# MZCAT_color_sensor.net
KiCad netlist of a schematic drawn in Altium Designer
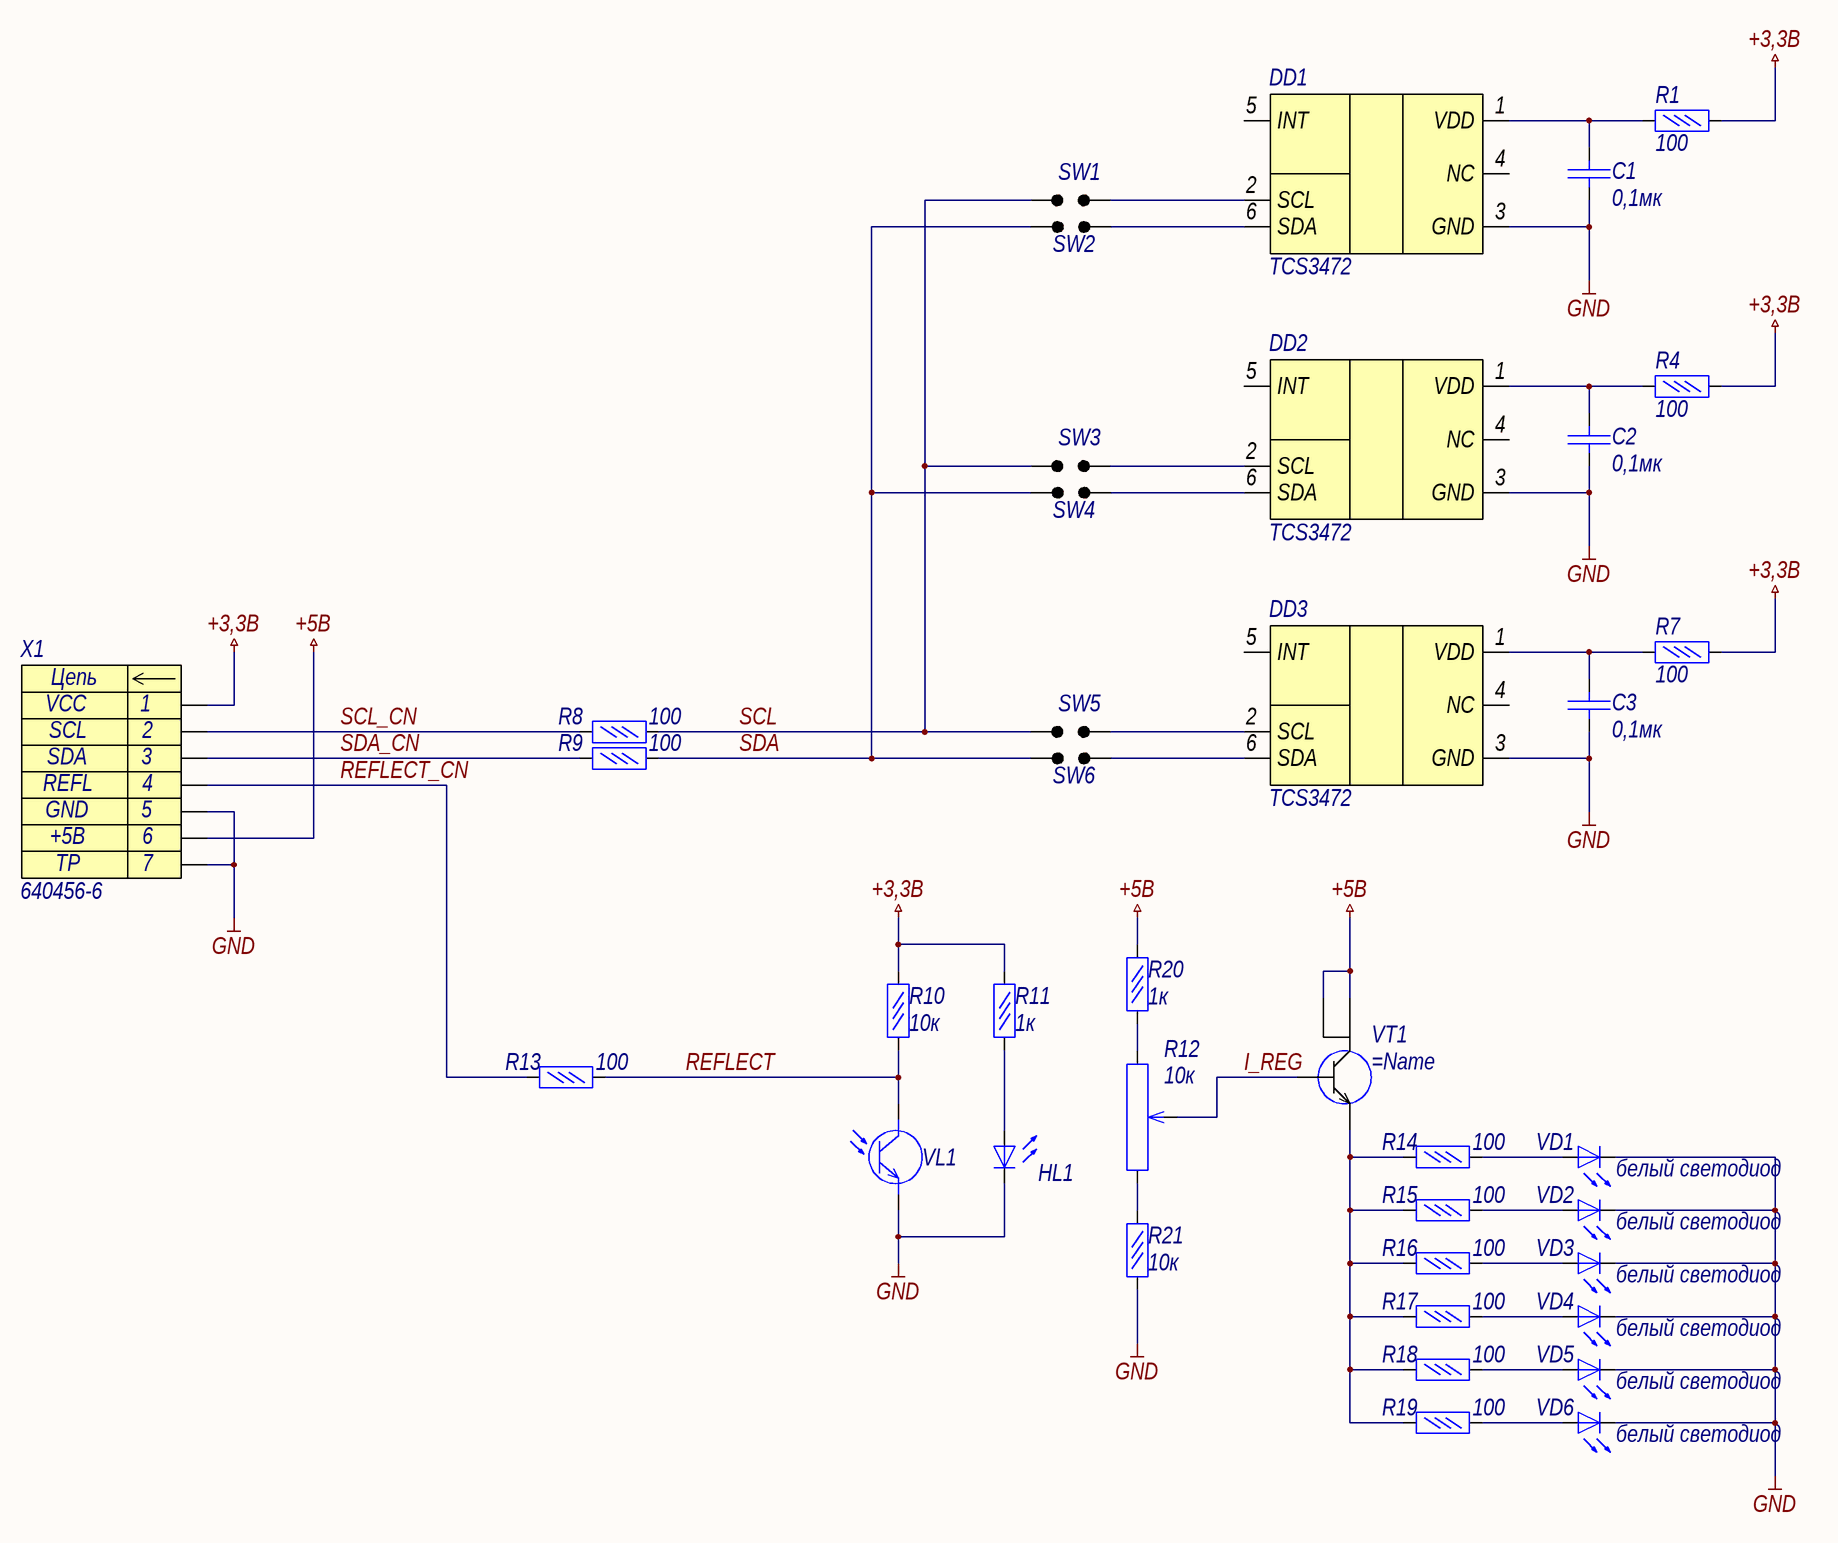
[diagram p0: MZCAT_color_sensor.SchDoc]

(export (version "E")
  (design (tool "Eeschema 10.0.6"))
  (components
    (comp (ref "DD1")
      (value "TCS3472")
      (footprint "TCS3472")
      (libsource (lib "MZBT_SchLibrary") (part "TCS3472"))
    )
    (comp (ref "DD2")
      (value "TCS3472")
      (footprint "TCS3472")
      (libsource (lib "MZBT_SchLibrary") (part "TCS3472"))
    )
    (comp (ref "DD3")
      (value "TCS3472")
      (footprint "TCS3472")
      (libsource (lib "MZBT_SchLibrary") (part "TCS3472"))
    )
    (comp (ref "HL1")
      (value "~")
      (footprint "LED 5mm")
      (description "инфракрасный светодиод")
      (libsource (lib "MZBT_SchLibrary") (part "ИК светодиод"))
    )
    (comp (ref "R1")
      (value "100")
      (footprint "R0603")
      (description "Резистор 0,05Вт")
      (libsource (lib "MZBT_SchLibrary") (part "Резистор 0.05Вт"))
    )
    (comp (ref "R4")
      (value "100")
      (footprint "R0603")
      (description "Резистор 0,05Вт")
      (libsource (lib "MZBT_SchLibrary") (part "Резистор 0.05Вт"))
    )
    (comp (ref "R7")
      (value "100")
      (footprint "R0603")
      (description "Резистор 0,05Вт")
      (libsource (lib "MZBT_SchLibrary") (part "Резистор 0.05Вт"))
    )
    (comp (ref "R8")
      (value "100")
      (footprint "R0603")
      (description "Резистор 0,05Вт")
      (libsource (lib "MZBT_SchLibrary") (part "Резистор 0.05Вт"))
    )
    (comp (ref "R9")
      (value "100")
      (footprint "R0603")
      (description "Резистор 0,05Вт")
      (libsource (lib "MZBT_SchLibrary") (part "Резистор 0.05Вт"))
    )
    (comp (ref "R10")
      (value "10к")
      (footprint "R0603")
      (description "Резистор 0,05Вт")
      (libsource (lib "") (part "Резистор 0.05Вт_1"))
    )
    (comp (ref "R11")
      (value "1к")
      (footprint "R0603")
      (description "Резистор 0,05Вт")
      (libsource (lib "") (part "Резистор 0.05Вт_1"))
    )
    (comp (ref "R12")
      (value "10к")
      (footprint "35W potentiometer")
      (libsource (lib "MZBT_SchLibrary") (part "потенциометр SMD"))
    )
    (comp (ref "R13")
      (value "100")
      (footprint "R0603")
      (description "Резистор 0,05Вт")
      (libsource (lib "MZBT_SchLibrary") (part "Резистор 0.05Вт"))
    )
    (comp (ref "R14")
      (value "100")
      (footprint "R0603")
      (description "Резистор 0,05Вт")
      (libsource (lib "MZBT_SchLibrary") (part "Резистор 0.05Вт"))
    )
    (comp (ref "R15")
      (value "100")
      (footprint "R0603")
      (description "Резистор 0,05Вт")
      (libsource (lib "MZBT_SchLibrary") (part "Резистор 0.05Вт"))
    )
    (comp (ref "R16")
      (value "100")
      (footprint "R0603")
      (description "Резистор 0,05Вт")
      (libsource (lib "MZBT_SchLibrary") (part "Резистор 0.05Вт"))
    )
    (comp (ref "R17")
      (value "100")
      (footprint "R0603")
      (description "Резистор 0,05Вт")
      (libsource (lib "MZBT_SchLibrary") (part "Резистор 0.05Вт"))
    )
    (comp (ref "R18")
      (value "100")
      (footprint "R0603")
      (description "Резистор 0,05Вт")
      (libsource (lib "MZBT_SchLibrary") (part "Резистор 0.05Вт"))
    )
    (comp (ref "R19")
      (value "100")
      (footprint "R0603")
      (description "Резистор 0,05Вт")
      (libsource (lib "MZBT_SchLibrary") (part "Резистор 0.05Вт"))
    )
    (comp (ref "R20")
      (value "1к")
      (footprint "R0603")
      (description "Резистор 0,05Вт")
      (libsource (lib "") (part "Резистор 0.05Вт_1"))
    )
    (comp (ref "R21")
      (value "10к")
      (footprint "R0603")
      (description "Резистор 0,05Вт")
      (libsource (lib "") (part "Резистор 0.05Вт_1"))
    )
    (comp (ref "SW1")
      (value "~")
      (footprint "JUMPER_SOLDERED_3x1")
      (description "Запаиваемая перемычка")
      (libsource (lib "mount_parts") (part "jumper"))
    )
    (comp (ref "SW2")
      (value "~")
      (footprint "JUMPER_SOLDERED_3x1")
      (description "Запаиваемая перемычка")
      (libsource (lib "mount_parts") (part "jumper"))
    )
    (comp (ref "SW3")
      (value "~")
      (footprint "JUMPER_SOLDERED_3x1")
      (description "Запаиваемая перемычка")
      (libsource (lib "mount_parts") (part "jumper"))
    )
    (comp (ref "SW4")
      (value "~")
      (footprint "JUMPER_SOLDERED_3x1")
      (description "Запаиваемая перемычка")
      (libsource (lib "mount_parts") (part "jumper"))
    )
    (comp (ref "SW5")
      (value "~")
      (footprint "JUMPER_SOLDERED_3x1")
      (description "Запаиваемая перемычка")
      (libsource (lib "mount_parts") (part "jumper"))
    )
    (comp (ref "SW6")
      (value "~")
      (footprint "JUMPER_SOLDERED_3x1")
      (description "Запаиваемая перемычка")
      (libsource (lib "mount_parts") (part "jumper"))
    )
    (comp (ref "VD1")
      (value "белый светодиод")
      (footprint "2835 led")
      (description "Светодтод SMD")
      (libsource (lib "MZBT_SchLibrary") (part "SMD светодиод"))
    )
    (comp (ref "VD2")
      (value "белый светодиод")
      (footprint "2835 led")
      (description "Светодтод SMD")
      (libsource (lib "MZBT_SchLibrary") (part "SMD светодиод"))
    )
    (comp (ref "VD3")
      (value "белый светодиод")
      (footprint "2835 led")
      (description "Светодтод SMD")
      (libsource (lib "MZBT_SchLibrary") (part "SMD светодиод"))
    )
    (comp (ref "VD4")
      (value "белый светодиод")
      (footprint "2835 led")
      (description "Светодтод SMD")
      (libsource (lib "MZBT_SchLibrary") (part "SMD светодиод"))
    )
    (comp (ref "VD5")
      (value "белый светодиод")
      (footprint "2835 led")
      (description "Светодтод SMD")
      (libsource (lib "MZBT_SchLibrary") (part "SMD светодиод"))
    )
    (comp (ref "VD6")
      (value "белый светодиод")
      (footprint "2835 led")
      (description "Светодтод SMD")
      (libsource (lib "MZBT_SchLibrary") (part "SMD светодиод"))
    )
    (comp (ref "VL1")
      (value "~")
      (footprint "LED 5mm")
      (libsource (lib "MZBT_SchLibrary") (part "фототранзистор"))
    )
    (comp (ref "VT1")
      (value "~")
      (footprint "SOT-223")
      (description "Биполярный транзистор, NPN, 40 В, 5 А, 2 Вт")
      (libsource (lib "MZBT_SchLibrary") (part "PBSS4540Z"))
    )
    (comp (ref "X1")
      (value "640456-6")
      (footprint "LCP 6 pin")
      (description "Разъем - 6 конт. мама")
      (libsource (lib "MZBT_SchLibrary") (part "Header_6"))
    )
    (comp (ref "С1")
      (value "0,1мк")
      (footprint "C0603")
      (libsource (lib "MZBT_SchLibrary") (part "Кер. конденсатор"))
    )
    (comp (ref "С2")
      (value "0,1мк")
      (footprint "C0603")
      (libsource (lib "MZBT_SchLibrary") (part "Кер. конденсатор"))
    )
    (comp (ref "С3")
      (value "0,1мк")
      (footprint "C0603")
      (libsource (lib "MZBT_SchLibrary") (part "Кер. конденсатор"))
    )
  )
  (nets
    (net (code "1") (name "+3,3В") (class "Default")
      (node (ref "R1") (pin "2") (pinfunction "2_2") (pintype "passive"))
      (node (ref "R10") (pin "2") (pinfunction "2_2") (pintype "passive"))
      (node (ref "R11") (pin "2") (pinfunction "2_2") (pintype "passive"))
      (node (ref "R4") (pin "2") (pinfunction "2_2") (pintype "passive"))
      (node (ref "R7") (pin "2") (pinfunction "2_2") (pintype "passive"))
      (node (ref "X1") (pin "1") (pinfunction "1_1") (pintype "passive"))
    )
    (net (code "2") (name "+5В") (class "Default")
      (node (ref "R20") (pin "2") (pinfunction "2_2") (pintype "passive"))
      (node (ref "VT1") (pin "2") (pinfunction "collector_2") (pintype "passive"))
      (node (ref "VT1") (pin "4") (pinfunction "collector_4") (pintype "passive"))
      (node (ref "X1") (pin "6") (pinfunction "6_6") (pintype "passive"))
    )
    (net (code "3") (name "/I_REG") (class "Default")
      (node (ref "R12") (pin "3") (pinfunction "3_3") (pintype "passive"))
      (node (ref "VT1") (pin "1") (pinfunction "base_1") (pintype "passive"))
    )
    (net (code "4") (name "/REFLECT") (class "Default")
      (node (ref "R10") (pin "1") (pinfunction "1_1") (pintype "passive"))
      (node (ref "R13") (pin "2") (pinfunction "2_2") (pintype "passive"))
      (node (ref "VL1") (pin "1") (pinfunction "C_1") (pintype "passive"))
    )
    (net (code "5") (name "/REFLECT_CN") (class "Default")
      (node (ref "R13") (pin "1") (pinfunction "1_1") (pintype "passive"))
      (node (ref "X1") (pin "4") (pinfunction "4_4") (pintype "passive"))
    )
    (net (code "6") (name "/SCL") (class "Default")
      (node (ref "R8") (pin "2") (pinfunction "2_2") (pintype "passive"))
      (node (ref "SW1") (pin "1") (pinfunction "1_1") (pintype "passive"))
      (node (ref "SW3") (pin "1") (pinfunction "1_1") (pintype "passive"))
      (node (ref "SW5") (pin "1") (pinfunction "1_1") (pintype "passive"))
    )
    (net (code "7") (name "/SCL_CN") (class "Default")
      (node (ref "R8") (pin "1") (pinfunction "1_1") (pintype "passive"))
      (node (ref "X1") (pin "2") (pinfunction "2_2") (pintype "passive"))
    )
    (net (code "8") (name "/SDA") (class "Default")
      (node (ref "R9") (pin "2") (pinfunction "2_2") (pintype "passive"))
      (node (ref "SW2") (pin "1") (pinfunction "1_1") (pintype "passive"))
      (node (ref "SW4") (pin "1") (pinfunction "1_1") (pintype "passive"))
      (node (ref "SW6") (pin "1") (pinfunction "1_1") (pintype "passive"))
    )
    (net (code "9") (name "/SDA_CN") (class "Default")
      (node (ref "R9") (pin "1") (pinfunction "1_1") (pintype "passive"))
      (node (ref "X1") (pin "3") (pinfunction "3_3") (pintype "passive"))
    )
    (net (code "10") (name "GND") (class "Default")
      (node (ref "DD1") (pin "3") (pinfunction "GND_3") (pintype "passive"))
      (node (ref "DD2") (pin "3") (pinfunction "GND_3") (pintype "passive"))
      (node (ref "DD3") (pin "3") (pinfunction "GND_3") (pintype "passive"))
      (node (ref "HL1") (pin "2") (pinfunction "K_2") (pintype "passive"))
      (node (ref "R21") (pin "1") (pinfunction "1_1") (pintype "passive"))
      (node (ref "VD1") (pin "2") (pinfunction "K_2") (pintype "passive"))
      (node (ref "VD2") (pin "2") (pinfunction "K_2") (pintype "passive"))
      (node (ref "VD3") (pin "2") (pinfunction "K_2") (pintype "passive"))
      (node (ref "VD4") (pin "2") (pinfunction "K_2") (pintype "passive"))
      (node (ref "VD5") (pin "2") (pinfunction "K_2") (pintype "passive"))
      (node (ref "VD6") (pin "2") (pinfunction "K_2") (pintype "passive"))
      (node (ref "VL1") (pin "2") (pinfunction "E_2") (pintype "passive"))
      (node (ref "X1") (pin "0") (pinfunction "0_0") (pintype "passive"))
      (node (ref "X1") (pin "5") (pinfunction "5_5") (pintype "passive"))
      (node (ref "С1") (pin "1") (pinfunction "1_1") (pintype "passive"))
      (node (ref "С2") (pin "1") (pinfunction "1_1") (pintype "passive"))
      (node (ref "С3") (pin "1") (pinfunction "1_1") (pintype "passive"))
    )
    (net (code "11") (name "Net-(DD1-SCL)") (class "Default")
      (node (ref "DD1") (pin "2") (pinfunction "SCL_2") (pintype "passive"))
      (node (ref "SW1") (pin "2") (pinfunction "2_2") (pintype "passive"))
    )
    (net (code "12") (name "Net-(DD1-SDA)") (class "Default")
      (node (ref "DD1") (pin "6") (pinfunction "SDA_6") (pintype "passive"))
      (node (ref "SW2") (pin "2") (pinfunction "2_2") (pintype "passive"))
    )
    (net (code "13") (name "Net-(DD1-VDD)") (class "Default")
      (node (ref "DD1") (pin "1") (pinfunction "VDD_1") (pintype "passive"))
      (node (ref "R1") (pin "1") (pinfunction "1_1") (pintype "passive"))
      (node (ref "С1") (pin "2") (pinfunction "2_2") (pintype "passive"))
    )
    (net (code "14") (name "Net-(DD2-SCL)") (class "Default")
      (node (ref "DD2") (pin "2") (pinfunction "SCL_2") (pintype "passive"))
      (node (ref "SW3") (pin "2") (pinfunction "2_2") (pintype "passive"))
    )
    (net (code "15") (name "Net-(DD2-SDA)") (class "Default")
      (node (ref "DD2") (pin "6") (pinfunction "SDA_6") (pintype "passive"))
      (node (ref "SW4") (pin "2") (pinfunction "2_2") (pintype "passive"))
    )
    (net (code "16") (name "Net-(DD2-VDD)") (class "Default")
      (node (ref "DD2") (pin "1") (pinfunction "VDD_1") (pintype "passive"))
      (node (ref "R4") (pin "1") (pinfunction "1_1") (pintype "passive"))
      (node (ref "С2") (pin "2") (pinfunction "2_2") (pintype "passive"))
    )
    (net (code "17") (name "Net-(DD3-SCL)") (class "Default")
      (node (ref "DD3") (pin "2") (pinfunction "SCL_2") (pintype "passive"))
      (node (ref "SW5") (pin "2") (pinfunction "2_2") (pintype "passive"))
    )
    (net (code "18") (name "Net-(DD3-SDA)") (class "Default")
      (node (ref "DD3") (pin "6") (pinfunction "SDA_6") (pintype "passive"))
      (node (ref "SW6") (pin "2") (pinfunction "2_2") (pintype "passive"))
    )
    (net (code "19") (name "Net-(DD3-VDD)") (class "Default")
      (node (ref "DD3") (pin "1") (pinfunction "VDD_1") (pintype "passive"))
      (node (ref "R7") (pin "1") (pinfunction "1_1") (pintype "passive"))
      (node (ref "С3") (pin "2") (pinfunction "2_2") (pintype "passive"))
    )
    (net (code "20") (name "Net-(HL1-A)") (class "Default")
      (node (ref "HL1") (pin "1") (pinfunction "A_1") (pintype "passive"))
      (node (ref "R11") (pin "1") (pinfunction "1_1") (pintype "passive"))
    )
    (net (code "21") (name "Net-(R12-Pad1)") (class "Default")
      (node (ref "R12") (pin "1") (pinfunction "1_1") (pintype "passive"))
      (node (ref "R20") (pin "1") (pinfunction "1_1") (pintype "passive"))
    )
    (net (code "22") (name "Net-(R12-Pad2)") (class "Default")
      (node (ref "R12") (pin "2") (pinfunction "2_2") (pintype "passive"))
      (node (ref "R21") (pin "2") (pinfunction "2_2") (pintype "passive"))
    )
    (net (code "23") (name "Net-(VD1-A)") (class "Default")
      (node (ref "R14") (pin "2") (pinfunction "2_2") (pintype "passive"))
      (node (ref "VD1") (pin "1") (pinfunction "A_1") (pintype "passive"))
    )
    (net (code "24") (name "Net-(VD2-A)") (class "Default")
      (node (ref "R15") (pin "2") (pinfunction "2_2") (pintype "passive"))
      (node (ref "VD2") (pin "1") (pinfunction "A_1") (pintype "passive"))
    )
    (net (code "25") (name "Net-(VD3-A)") (class "Default")
      (node (ref "R16") (pin "2") (pinfunction "2_2") (pintype "passive"))
      (node (ref "VD3") (pin "1") (pinfunction "A_1") (pintype "passive"))
    )
    (net (code "26") (name "Net-(VD4-A)") (class "Default")
      (node (ref "R17") (pin "2") (pinfunction "2_2") (pintype "passive"))
      (node (ref "VD4") (pin "1") (pinfunction "A_1") (pintype "passive"))
    )
    (net (code "27") (name "Net-(VD5-A)") (class "Default")
      (node (ref "R18") (pin "2") (pinfunction "2_2") (pintype "passive"))
      (node (ref "VD5") (pin "1") (pinfunction "A_1") (pintype "passive"))
    )
    (net (code "28") (name "Net-(VD6-A)") (class "Default")
      (node (ref "R19") (pin "2") (pinfunction "2_2") (pintype "passive"))
      (node (ref "VD6") (pin "1") (pinfunction "A_1") (pintype "passive"))
    )
    (net (code "29") (name "Net-(VT1-emitter)") (class "Default")
      (node (ref "R14") (pin "1") (pinfunction "1_1") (pintype "passive"))
      (node (ref "R15") (pin "1") (pinfunction "1_1") (pintype "passive"))
      (node (ref "R16") (pin "1") (pinfunction "1_1") (pintype "passive"))
      (node (ref "R17") (pin "1") (pinfunction "1_1") (pintype "passive"))
      (node (ref "R18") (pin "1") (pinfunction "1_1") (pintype "passive"))
      (node (ref "R19") (pin "1") (pinfunction "1_1") (pintype "passive"))
      (node (ref "VT1") (pin "3") (pinfunction "emitter_3") (pintype "passive"))
    )
    (net (code "30") (name "unconnected-(DD1-INT-Pad5)") (class "Default")
      (node (ref "DD1") (pin "5") (pinfunction "INT_5") (pintype "passive"))
    )
    (net (code "31") (name "unconnected-(DD1-NC-Pad4)") (class "Default")
      (node (ref "DD1") (pin "4") (pinfunction "NC_4") (pintype "passive"))
    )
    (net (code "32") (name "unconnected-(DD2-INT-Pad5)") (class "Default")
      (node (ref "DD2") (pin "5") (pinfunction "INT_5") (pintype "passive"))
    )
    (net (code "33") (name "unconnected-(DD2-NC-Pad4)") (class "Default")
      (node (ref "DD2") (pin "4") (pinfunction "NC_4") (pintype "passive"))
    )
    (net (code "34") (name "unconnected-(DD3-INT-Pad5)") (class "Default")
      (node (ref "DD3") (pin "5") (pinfunction "INT_5") (pintype "passive"))
    )
    (net (code "35") (name "unconnected-(DD3-NC-Pad4)") (class "Default")
      (node (ref "DD3") (pin "4") (pinfunction "NC_4") (pintype "passive"))
    )
  )
)
